# RF_Protoboard.net
KiCad netlist of a schematic drawn in Altium Designer
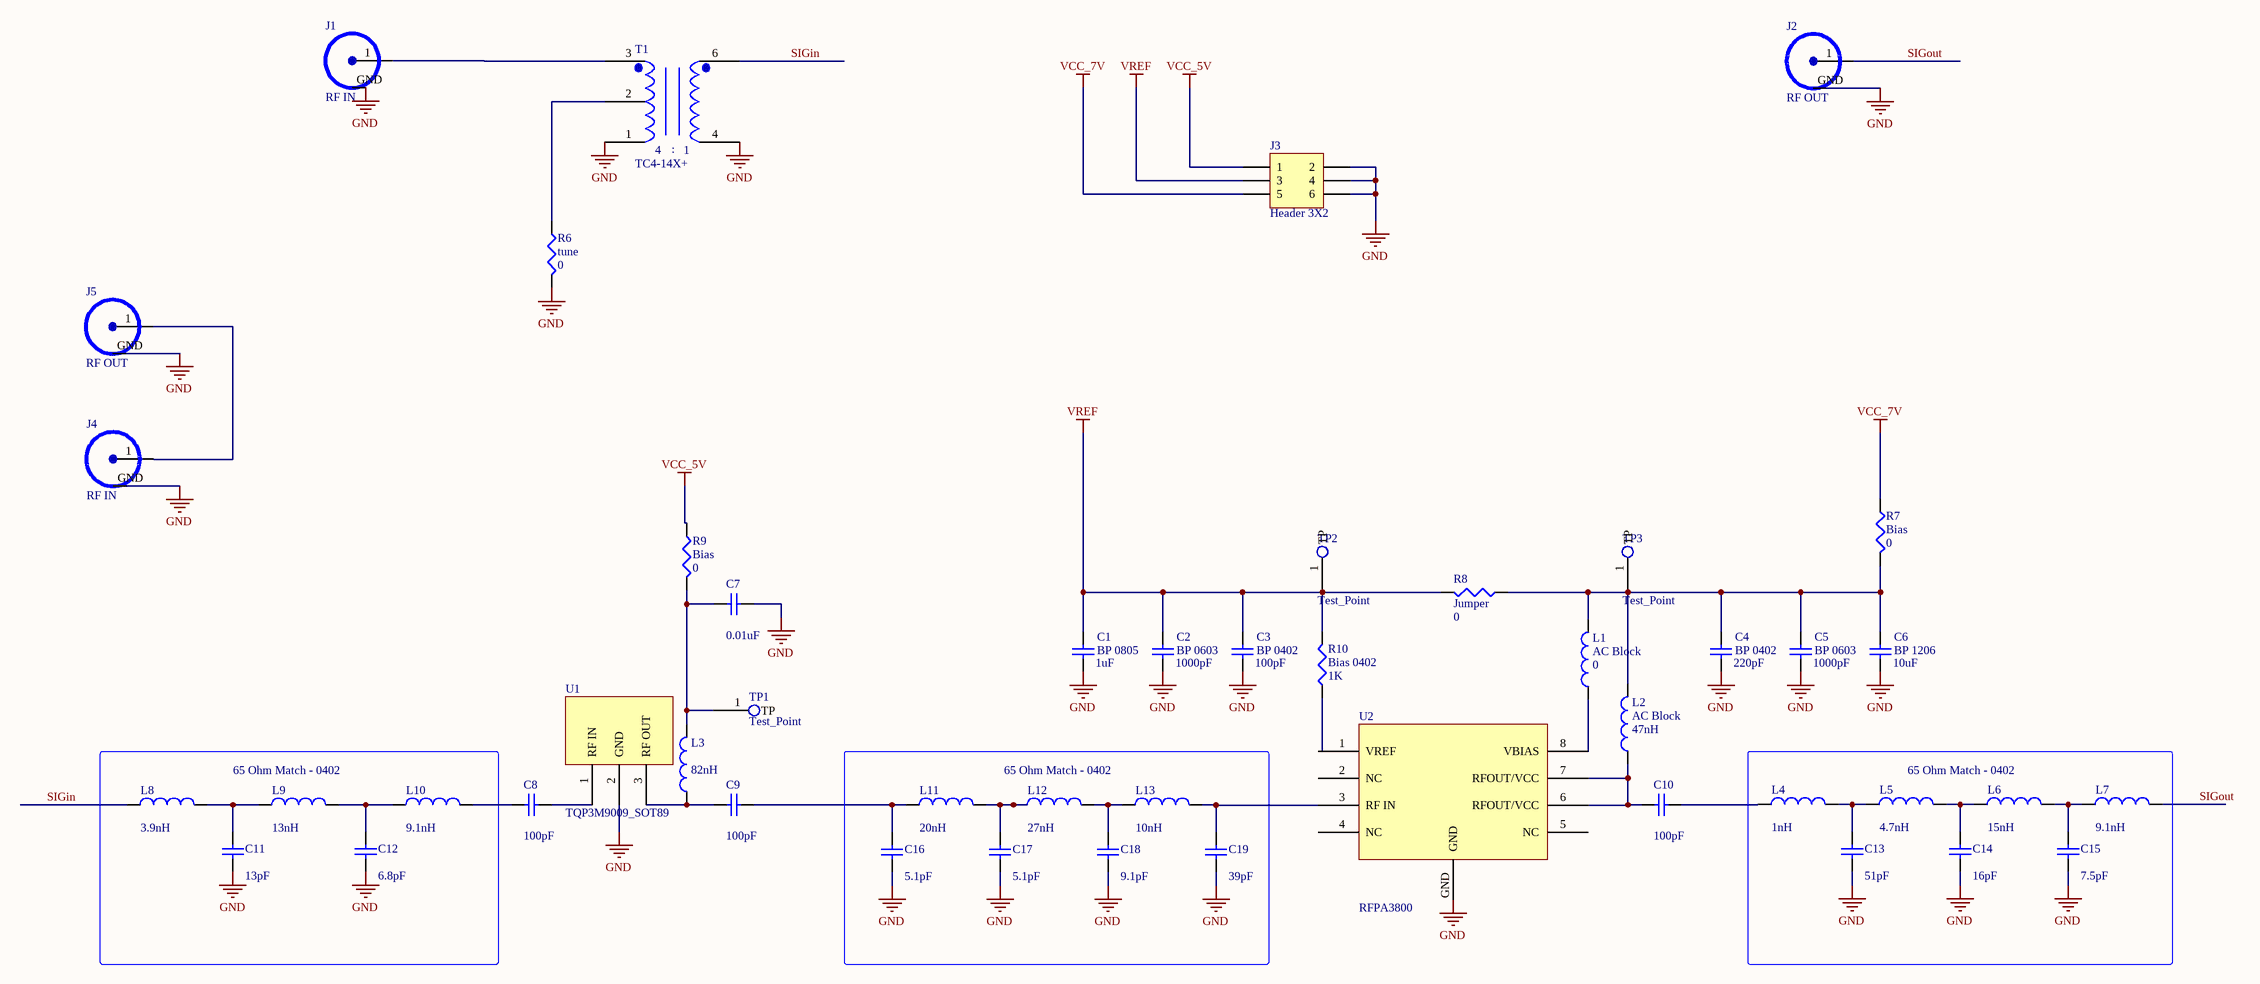
[diagram p0: RF_Protoboard.SchDoc]

(export (version "E")
  (design (tool "Eeschema 10.0.6"))
  (components
    (comp (ref "C1")
      (value "BP 0805")
      (footprint "0805_SMT")
      (description "Capacitor")
      (fields (field (name "ALTIUM_VALUE") "1uF") (field (name "PUBLISHER") "Altium Limited"))
      (libsource (lib "Miscellaneous Devices") (part "Cap"))
    )
    (comp (ref "C2")
      (value "BP 0603")
      (footprint "0603_SMT")
      (description "Capacitor")
      (fields (field (name "ALTIUM_VALUE") "1000pF") (field (name "PUBLISHER") "Altium Limited"))
      (libsource (lib "Miscellaneous Devices") (part "Cap"))
    )
    (comp (ref "C3")
      (value "BP 0402")
      (footprint "0402_SMT")
      (description "Capacitor")
      (fields (field (name "ALTIUM_VALUE") "100pF") (field (name "PUBLISHER") "Altium Limited"))
      (libsource (lib "Miscellaneous Devices") (part "Cap"))
    )
    (comp (ref "C4")
      (value "BP 0402")
      (footprint "0402_SMT")
      (description "Capacitor")
      (fields (field (name "ALTIUM_VALUE") "220pF") (field (name "PUBLISHER") "Altium Limited"))
      (libsource (lib "Miscellaneous Devices") (part "Cap"))
    )
    (comp (ref "C5")
      (value "BP 0603")
      (footprint "0603_SMT")
      (description "Capacitor")
      (fields (field (name "ALTIUM_VALUE") "1000pF") (field (name "PUBLISHER") "Altium Limited"))
      (libsource (lib "Miscellaneous Devices") (part "Cap"))
    )
    (comp (ref "C6")
      (value "BP 1206")
      (footprint "0805_SMT")
      (description "Capacitor")
      (fields (field (name "ALTIUM_VALUE") "10uF") (field (name "PUBLISHER") "Altium Limited"))
      (libsource (lib "Miscellaneous Devices") (part "Cap"))
    )
    (comp (ref "C7")
      (value "0.01uF")
      (footprint "0402_SMT")
      (description "Capacitor")
      (fields (field (name "Comment") "Cap") (field (name "PUBLISHER") "Altium Limited"))
      (libsource (lib "Miscellaneous Devices") (part "Cap"))
    )
    (comp (ref "C8")
      (value "100pF")
      (footprint "0402_SMT")
      (description "Capacitor")
      (fields (field (name "Comment") "Cap") (field (name "PUBLISHER") "Altium Limited"))
      (libsource (lib "Miscellaneous Devices") (part "Cap"))
    )
    (comp (ref "C9")
      (value "100pF")
      (footprint "0402_SMT")
      (description "Capacitor")
      (fields (field (name "Comment") "Cap") (field (name "PUBLISHER") "Altium Limited"))
      (libsource (lib "Miscellaneous Devices") (part "Cap"))
    )
    (comp (ref "C10")
      (value "100pF")
      (footprint "0402_SMT")
      (description "Capacitor")
      (fields (field (name "Comment") "Cap") (field (name "PUBLISHER") "Altium Limited"))
      (libsource (lib "Miscellaneous Devices") (part "Cap"))
    )
    (comp (ref "C11")
      (value "13pF")
      (footprint "0402_SMT")
      (description "Capacitor")
      (fields (field (name "Comment") "Cap") (field (name "PUBLISHER") "Altium Limited"))
      (libsource (lib "Miscellaneous Devices") (part "Cap"))
    )
    (comp (ref "C12")
      (value "6.8pF")
      (footprint "0402_SMT")
      (description "Capacitor")
      (fields (field (name "Comment") "Cap") (field (name "PUBLISHER") "Altium Limited"))
      (libsource (lib "Miscellaneous Devices") (part "Cap"))
    )
    (comp (ref "C13")
      (value "51pF")
      (footprint "0402_SMT")
      (description "Capacitor")
      (fields (field (name "Comment") "Cap") (field (name "PUBLISHER") "Altium Limited"))
      (libsource (lib "Miscellaneous Devices") (part "Cap"))
    )
    (comp (ref "C14")
      (value "16pF")
      (footprint "0402_SMT")
      (description "Capacitor")
      (fields (field (name "Comment") "Cap") (field (name "PUBLISHER") "Altium Limited"))
      (libsource (lib "Miscellaneous Devices") (part "Cap"))
    )
    (comp (ref "C15")
      (value "7.5pF")
      (footprint "0402_SMT")
      (description "Capacitor")
      (fields (field (name "Comment") "Cap") (field (name "PUBLISHER") "Altium Limited"))
      (libsource (lib "Miscellaneous Devices") (part "Cap"))
    )
    (comp (ref "C16")
      (value "5.1pF")
      (footprint "0402_SMT")
      (description "Capacitor")
      (fields (field (name "Comment") "Cap") (field (name "PUBLISHER") "Altium Limited"))
      (libsource (lib "Miscellaneous Devices") (part "Cap"))
    )
    (comp (ref "C17")
      (value "5.1pF")
      (footprint "0402_SMT")
      (description "Capacitor")
      (fields (field (name "Comment") "Cap") (field (name "PUBLISHER") "Altium Limited"))
      (libsource (lib "Miscellaneous Devices") (part "Cap"))
    )
    (comp (ref "C18")
      (value "9.1pF")
      (footprint "0402_SMT")
      (description "Capacitor")
      (fields (field (name "Comment") "Cap") (field (name "PUBLISHER") "Altium Limited"))
      (libsource (lib "Miscellaneous Devices") (part "Cap"))
    )
    (comp (ref "C19")
      (value "39pF")
      (footprint "0402_SMT")
      (description "Capacitor")
      (fields (field (name "Comment") "Cap") (field (name "PUBLISHER") "Altium Limited"))
      (libsource (lib "Miscellaneous Devices") (part "Cap"))
    )
    (comp (ref "J1")
      (value "RF IN")
      (footprint "SMA_Edge_Launch")
      (description "Edge-Launch SMA Female")
      (libsource (lib "RNG_Parts") (part "SMA-Edge-Launch"))
    )
    (comp (ref "J2")
      (value "RF OUT")
      (footprint "SMA_Edge_Launch")
      (description "Edge-Launch SMA Female")
      (libsource (lib "RNG_Parts") (part "SMA-Edge-Launch"))
    )
    (comp (ref "J3")
      (value "Header 3X2")
      (footprint "HDR2X3")
      (description "Header, 3-Pin, Dual row")
      (fields (field (name "PUBLISHER") "Altium Limited"))
      (libsource (lib "Miscellaneous Connectors") (part "Header 3X2"))
    )
    (comp (ref "J4")
      (value "RF IN")
      (footprint "SMA_Edge_Launch")
      (description "Edge-Launch SMA Female")
      (libsource (lib "RNG_Parts") (part "SMA-Edge-Launch"))
    )
    (comp (ref "J5")
      (value "RF OUT")
      (footprint "SMA_Edge_Launch")
      (description "Edge-Launch SMA Female")
      (libsource (lib "RNG_Parts") (part "SMA-Edge-Launch"))
    )
    (comp (ref "L1")
      (value "AC Block")
      (footprint "0402_SMT")
      (description "Inductor")
      (fields (field (name "ALTIUM_VALUE") "0") (field (name "PUBLISHER") "Altium Limited"))
      (libsource (lib "Miscellaneous Devices") (part "Inductor"))
    )
    (comp (ref "L2")
      (value "AC Block")
      (footprint "0402_SMT")
      (description "Inductor")
      (fields (field (name "ALTIUM_VALUE") "47nH") (field (name "PUBLISHER") "Altium Limited"))
      (libsource (lib "Miscellaneous Devices") (part "Inductor"))
    )
    (comp (ref "L3")
      (value "82nH")
      (footprint "0402_SMT")
      (description "Inductor")
      (fields (field (name "PUBLISHER") "Altium Limited"))
      (libsource (lib "Miscellaneous Devices") (part "Inductor"))
    )
    (comp (ref "L4")
      (value "1nH")
      (footprint "0402_SMT")
      (description "Inductor")
      (fields (field (name "PUBLISHER") "Altium Limited"))
      (libsource (lib "Miscellaneous Devices") (part "Inductor"))
    )
    (comp (ref "L5")
      (value "4.7nH")
      (footprint "0402_SMT")
      (description "Inductor")
      (fields (field (name "PUBLISHER") "Altium Limited"))
      (libsource (lib "Miscellaneous Devices") (part "Inductor"))
    )
    (comp (ref "L6")
      (value "15nH")
      (footprint "0402_SMT")
      (description "Inductor")
      (fields (field (name "PUBLISHER") "Altium Limited"))
      (libsource (lib "Miscellaneous Devices") (part "Inductor"))
    )
    (comp (ref "L7")
      (value "9.1nH")
      (footprint "0402_SMT")
      (description "Inductor")
      (fields (field (name "PUBLISHER") "Altium Limited"))
      (libsource (lib "Miscellaneous Devices") (part "Inductor"))
    )
    (comp (ref "L8")
      (value "3.9nH")
      (footprint "0402_SMT")
      (description "Inductor")
      (fields (field (name "PUBLISHER") "Altium Limited"))
      (libsource (lib "Miscellaneous Devices") (part "Inductor"))
    )
    (comp (ref "L9")
      (value "13nH")
      (footprint "0402_SMT")
      (description "Inductor")
      (fields (field (name "PUBLISHER") "Altium Limited"))
      (libsource (lib "Miscellaneous Devices") (part "Inductor"))
    )
    (comp (ref "L10")
      (value "9.1nH")
      (footprint "0402_SMT")
      (description "Inductor")
      (fields (field (name "PUBLISHER") "Altium Limited"))
      (libsource (lib "Miscellaneous Devices") (part "Inductor"))
    )
    (comp (ref "L11")
      (value "20nH")
      (footprint "0402_SMT")
      (description "Inductor")
      (fields (field (name "PUBLISHER") "Altium Limited"))
      (libsource (lib "Miscellaneous Devices") (part "Inductor"))
    )
    (comp (ref "L12")
      (value "27nH")
      (footprint "0402_SMT")
      (description "Inductor")
      (fields (field (name "PUBLISHER") "Altium Limited"))
      (libsource (lib "Miscellaneous Devices") (part "Inductor"))
    )
    (comp (ref "L13")
      (value "10nH")
      (footprint "0402_SMT")
      (description "Inductor")
      (fields (field (name "PUBLISHER") "Altium Limited"))
      (libsource (lib "Miscellaneous Devices") (part "Inductor"))
    )
    (comp (ref "R6")
      (value "tune")
      (footprint "0402_SMT")
      (description "Resistor")
      (fields (field (name "ALTIUM_VALUE") "0") (field (name "PUBLISHER") "Altium Limited"))
      (libsource (lib "Miscellaneous Devices") (part "Res3"))
    )
    (comp (ref "R7")
      (value "Bias")
      (footprint "0402_SMT")
      (description "Resistor")
      (fields (field (name "ALTIUM_VALUE") "0") (field (name "PUBLISHER") "Altium Limited"))
      (libsource (lib "Miscellaneous Devices") (part "Res3"))
    )
    (comp (ref "R8")
      (value "Jumper")
      (footprint "0402_SMT")
      (description "Resistor")
      (fields (field (name "ALTIUM_VALUE") "0") (field (name "PUBLISHER") "Altium Limited"))
      (libsource (lib "Miscellaneous Devices") (part "Res3"))
    )
    (comp (ref "R9")
      (value "Bias")
      (footprint "0402_SMT")
      (description "Resistor")
      (fields (field (name "ALTIUM_VALUE") "0") (field (name "PUBLISHER") "Altium Limited"))
      (libsource (lib "Miscellaneous Devices") (part "Res3"))
    )
    (comp (ref "R10")
      (value "Bias 0402")
      (footprint "0402_SMT")
      (description "Resistor")
      (fields (field (name "ALTIUM_VALUE") "1K") (field (name "PUBLISHER") "Altium Limited"))
      (libsource (lib "Miscellaneous Devices") (part "Res3"))
    )
    (comp (ref "T1")
      (value "TC4-14X+")
      (footprint "AT224-1")
      (description "Mini-Circuits Type A Transformer, 4:1 Ohm, CT")
      (fields (field (name "MANUFACTURER") "Mini-Circuits"))
      (libsource (lib "RNG_Parts") (part "TC4-14+"))
    )
    (comp (ref "TP1")
      (value "Test_Point")
      (footprint "Test_Point")
      (description "Test Point")
      (libsource (lib "RNG_Parts") (part "Test_Point"))
    )
    (comp (ref "TP2")
      (value "Test_Point")
      (footprint "Test_Point")
      (description "Test Point")
      (libsource (lib "RNG_Parts") (part "Test_Point"))
    )
    (comp (ref "TP3")
      (value "Test_Point")
      (footprint "Test_Point")
      (description "Test Point")
      (libsource (lib "RNG_Parts") (part "Test_Point"))
    )
    (comp (ref "U1")
      (value "TQP3M9009_SOT89")
      (footprint "TQP3M9009_SOT-89")
      (description "Triquint TQP3M9009 Power Amplifier")
      (libsource (lib "RNG_Parts") (part "TQP3M9009_SOT89"))
    )
    (comp (ref "U2")
      (value "RFPA3800")
      (footprint "RFPA3800_SOIC-8")
      (description "RFMD RFPA3800 Power Amplifier")
      (fields (field (name "MANUFACTURER") "RFMD"))
      (libsource (lib "RNG_Parts") (part "RFPA3800"))
    )
  )
  (nets
    (net (code "1") (name "/SIGin") (class "Default")
      (node (ref "L8") (pin "1") (pinfunction "1_1") (pintype "passive"))
      (node (ref "T1") (pin "6") (pinfunction "P_DOT_6") (pintype "power_in"))
    )
    (net (code "2") (name "/SIGout") (class "Default")
      (node (ref "J2") (pin "1") (pinfunction "SIG_1") (pintype "power_in"))
      (node (ref "L7") (pin "2") (pinfunction "2_2") (pintype "passive"))
    )
    (net (code "3") (name "GND") (class "Default")
      (node (ref "C1") (pin "1") (pinfunction "1_1") (pintype "passive"))
      (node (ref "C11") (pin "1") (pinfunction "1_1") (pintype "passive"))
      (node (ref "C12") (pin "1") (pinfunction "1_1") (pintype "passive"))
      (node (ref "C13") (pin "1") (pinfunction "1_1") (pintype "passive"))
      (node (ref "C14") (pin "1") (pinfunction "1_1") (pintype "passive"))
      (node (ref "C15") (pin "1") (pinfunction "1_1") (pintype "passive"))
      (node (ref "C16") (pin "1") (pinfunction "1_1") (pintype "passive"))
      (node (ref "C17") (pin "1") (pinfunction "1_1") (pintype "passive"))
      (node (ref "C18") (pin "1") (pinfunction "1_1") (pintype "passive"))
      (node (ref "C19") (pin "1") (pinfunction "1_1") (pintype "passive"))
      (node (ref "C2") (pin "1") (pinfunction "1_1") (pintype "passive"))
      (node (ref "C3") (pin "1") (pinfunction "1_1") (pintype "passive"))
      (node (ref "C4") (pin "1") (pinfunction "1_1") (pintype "passive"))
      (node (ref "C5") (pin "1") (pinfunction "1_1") (pintype "passive"))
      (node (ref "C6") (pin "1") (pinfunction "1_1") (pintype "passive"))
      (node (ref "C7") (pin "2") (pinfunction "2_2") (pintype "passive"))
      (node (ref "J1") (pin "GND") (pinfunction "GND_GND") (pintype "power_in"))
      (node (ref "J2") (pin "GND") (pinfunction "GND_GND") (pintype "power_in"))
      (node (ref "J3") (pin "2") (pinfunction "2_2") (pintype "passive"))
      (node (ref "J3") (pin "4") (pinfunction "4_4") (pintype "passive"))
      (node (ref "J3") (pin "6") (pinfunction "6_6") (pintype "passive"))
      (node (ref "J4") (pin "GND") (pinfunction "GND_GND") (pintype "power_in"))
      (node (ref "J5") (pin "GND") (pinfunction "GND_GND") (pintype "power_in"))
      (node (ref "R6") (pin "2") (pinfunction "2_2") (pintype "passive"))
      (node (ref "T1") (pin "1") (pinfunction "S_1") (pintype "power_in"))
      (node (ref "T1") (pin "4") (pinfunction "P_4") (pintype "power_in"))
      (node (ref "U1") (pin "2") (pinfunction "GND_2") (pintype "passive"))
      (node (ref "U2") (pin "GND") (pinfunction "GND_GND") (pintype "passive"))
    )
    (net (code "4") (name "Net-(C8-Pad1)") (class "Default")
      (node (ref "C8") (pin "1") (pinfunction "1_1") (pintype "passive"))
      (node (ref "L10") (pin "2") (pinfunction "2_2") (pintype "passive"))
    )
    (net (code "5") (name "Net-(C10-Pad1)") (class "Default")
      (node (ref "C10") (pin "1") (pinfunction "1_1") (pintype "passive"))
      (node (ref "L2") (pin "1") (pinfunction "1_1") (pintype "passive"))
      (node (ref "U2") (pin "6") (pinfunction "RFOUT/VCC_6") (pintype "passive"))
      (node (ref "U2") (pin "7") (pinfunction "RFOUT/VCC_7") (pintype "passive"))
    )
    (net (code "6") (name "Net-(C10-Pad2)") (class "Default")
      (node (ref "C10") (pin "2") (pinfunction "2_2") (pintype "passive"))
      (node (ref "L4") (pin "1") (pinfunction "1_1") (pintype "passive"))
    )
    (net (code "7") (name "Net-(C11-Pad2)") (class "Default")
      (node (ref "C11") (pin "2") (pinfunction "2_2") (pintype "passive"))
      (node (ref "L8") (pin "2") (pinfunction "2_2") (pintype "passive"))
      (node (ref "L9") (pin "1") (pinfunction "1_1") (pintype "passive"))
    )
    (net (code "8") (name "Net-(C12-Pad2)") (class "Default")
      (node (ref "C12") (pin "2") (pinfunction "2_2") (pintype "passive"))
      (node (ref "L10") (pin "1") (pinfunction "1_1") (pintype "passive"))
      (node (ref "L9") (pin "2") (pinfunction "2_2") (pintype "passive"))
    )
    (net (code "9") (name "Net-(C13-Pad2)") (class "Default")
      (node (ref "C13") (pin "2") (pinfunction "2_2") (pintype "passive"))
      (node (ref "L4") (pin "2") (pinfunction "2_2") (pintype "passive"))
      (node (ref "L5") (pin "1") (pinfunction "1_1") (pintype "passive"))
    )
    (net (code "10") (name "Net-(C14-Pad2)") (class "Default")
      (node (ref "C14") (pin "2") (pinfunction "2_2") (pintype "passive"))
      (node (ref "L5") (pin "2") (pinfunction "2_2") (pintype "passive"))
      (node (ref "L6") (pin "1") (pinfunction "1_1") (pintype "passive"))
    )
    (net (code "11") (name "Net-(C15-Pad2)") (class "Default")
      (node (ref "C15") (pin "2") (pinfunction "2_2") (pintype "passive"))
      (node (ref "L6") (pin "2") (pinfunction "2_2") (pintype "passive"))
      (node (ref "L7") (pin "1") (pinfunction "1_1") (pintype "passive"))
    )
    (net (code "12") (name "Net-(C16-Pad2)") (class "Default")
      (node (ref "C16") (pin "2") (pinfunction "2_2") (pintype "passive"))
      (node (ref "C9") (pin "2") (pinfunction "2_2") (pintype "passive"))
      (node (ref "L11") (pin "1") (pinfunction "1_1") (pintype "passive"))
    )
    (net (code "13") (name "Net-(C17-Pad2)") (class "Default")
      (node (ref "C17") (pin "2") (pinfunction "2_2") (pintype "passive"))
      (node (ref "L11") (pin "2") (pinfunction "2_2") (pintype "passive"))
      (node (ref "L12") (pin "1") (pinfunction "1_1") (pintype "passive"))
    )
    (net (code "14") (name "Net-(C18-Pad2)") (class "Default")
      (node (ref "C18") (pin "2") (pinfunction "2_2") (pintype "passive"))
      (node (ref "L12") (pin "2") (pinfunction "2_2") (pintype "passive"))
      (node (ref "L13") (pin "1") (pinfunction "1_1") (pintype "passive"))
    )
    (net (code "15") (name "Net-(J1-SIG)") (class "Default")
      (node (ref "J1") (pin "1") (pinfunction "SIG_1") (pintype "power_in"))
      (node (ref "T1") (pin "3") (pinfunction "S_DOT_3") (pintype "power_in"))
    )
    (net (code "16") (name "Net-(J4-SIG)") (class "Default")
      (node (ref "J4") (pin "1") (pinfunction "SIG_1") (pintype "power_in"))
      (node (ref "J5") (pin "1") (pinfunction "SIG_1") (pintype "power_in"))
    )
    (net (code "17") (name "Net-(T1-S_CT)") (class "Default")
      (node (ref "R6") (pin "1") (pinfunction "1_1") (pintype "passive"))
      (node (ref "T1") (pin "2") (pinfunction "S_CT_2") (pintype "power_in"))
    )
    (net (code "18") (name "Net-(TP1-TP)") (class "Default")
      (node (ref "C7") (pin "1") (pinfunction "1_1") (pintype "passive"))
      (node (ref "L3") (pin "2") (pinfunction "2_2") (pintype "passive"))
      (node (ref "R9") (pin "2") (pinfunction "2_2") (pintype "passive"))
      (node (ref "TP1") (pin "1") (pinfunction "TP_1") (pintype "passive"))
    )
    (net (code "19") (name "Net-(TP3-TP)") (class "Default")
      (node (ref "C4") (pin "2") (pinfunction "2_2") (pintype "passive"))
      (node (ref "C5") (pin "2") (pinfunction "2_2") (pintype "passive"))
      (node (ref "C6") (pin "2") (pinfunction "2_2") (pintype "passive"))
      (node (ref "L1") (pin "2") (pinfunction "2_2") (pintype "passive"))
      (node (ref "L2") (pin "2") (pinfunction "2_2") (pintype "passive"))
      (node (ref "R7") (pin "2") (pinfunction "2_2") (pintype "passive"))
      (node (ref "R8") (pin "1") (pinfunction "1_1") (pintype "passive"))
      (node (ref "TP3") (pin "1") (pinfunction "TP_1") (pintype "passive"))
    )
    (net (code "20") (name "Net-(U1-RF_IN)") (class "Default")
      (node (ref "C8") (pin "2") (pinfunction "2_2") (pintype "passive"))
      (node (ref "U1") (pin "1") (pinfunction "RF_IN_1") (pintype "passive"))
    )
    (net (code "21") (name "Net-(U1-RF_OUT)") (class "Default")
      (node (ref "C9") (pin "1") (pinfunction "1_1") (pintype "passive"))
      (node (ref "L3") (pin "1") (pinfunction "1_1") (pintype "passive"))
      (node (ref "U1") (pin "3") (pinfunction "RF_OUT_3") (pintype "passive"))
    )
    (net (code "22") (name "Net-(U2-RF_IN)") (class "Default")
      (node (ref "C19") (pin "2") (pinfunction "2_2") (pintype "passive"))
      (node (ref "L13") (pin "2") (pinfunction "2_2") (pintype "passive"))
      (node (ref "U2") (pin "3") (pinfunction "RF_IN_3") (pintype "passive"))
    )
    (net (code "23") (name "Net-(U2-VBIAS)") (class "Default")
      (node (ref "L1") (pin "1") (pinfunction "1_1") (pintype "passive"))
      (node (ref "U2") (pin "8") (pinfunction "VBIAS_8") (pintype "passive"))
    )
    (net (code "24") (name "Net-(U2-VREF)") (class "Default")
      (node (ref "R10") (pin "1") (pinfunction "1_1") (pintype "passive"))
      (node (ref "U2") (pin "1") (pinfunction "VREF_1") (pintype "passive"))
    )
    (net (code "25") (name "VCC_5V") (class "Default")
      (node (ref "J3") (pin "1") (pinfunction "1_1") (pintype "passive"))
      (node (ref "R9") (pin "1") (pinfunction "1_1") (pintype "passive"))
    )
    (net (code "26") (name "VCC_7V") (class "Default")
      (node (ref "J3") (pin "5") (pinfunction "5_5") (pintype "passive"))
      (node (ref "R7") (pin "1") (pinfunction "1_1") (pintype "passive"))
    )
    (net (code "27") (name "VREF") (class "Default")
      (node (ref "C1") (pin "2") (pinfunction "2_2") (pintype "passive"))
      (node (ref "C2") (pin "2") (pinfunction "2_2") (pintype "passive"))
      (node (ref "C3") (pin "2") (pinfunction "2_2") (pintype "passive"))
      (node (ref "J3") (pin "3") (pinfunction "3_3") (pintype "passive"))
      (node (ref "R10") (pin "2") (pinfunction "2_2") (pintype "passive"))
      (node (ref "R8") (pin "2") (pinfunction "2_2") (pintype "passive"))
      (node (ref "TP2") (pin "1") (pinfunction "TP_1") (pintype "passive"))
    )
    (net (code "28") (name "unconnected-(U2-NC-Pad2)") (class "Default")
      (node (ref "U2") (pin "2") (pinfunction "NC_2") (pintype "passive"))
    )
    (net (code "29") (name "unconnected-(U2-NC-Pad4)") (class "Default")
      (node (ref "U2") (pin "4") (pinfunction "NC_4") (pintype "passive"))
    )
    (net (code "30") (name "unconnected-(U2-NC-Pad5)") (class "Default")
      (node (ref "U2") (pin "5") (pinfunction "NC_5") (pintype "passive"))
    )
  )
)
